# MotorDriver.net
KiCad netlist of a schematic drawn in Altium Designer
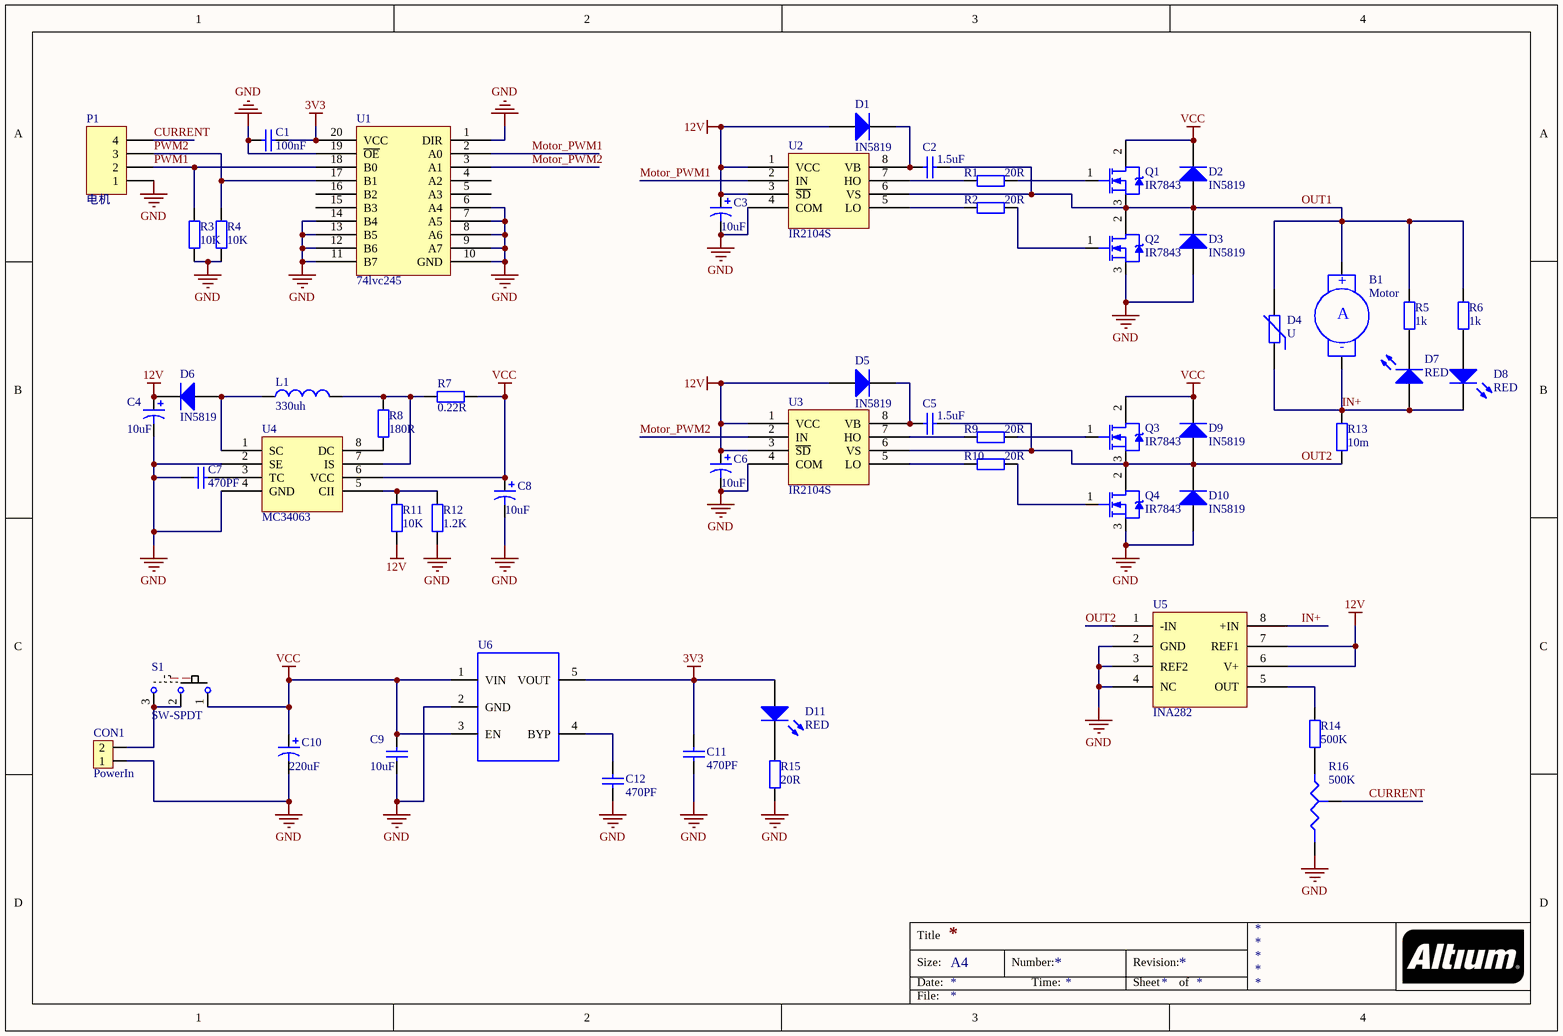
[diagram p0: MotorDriver.SchDoc]

(export (version "E")
  (design (tool "Eeschema 10.0.6"))
  (components
    (comp (ref "B1")
      (value "Motor")
      (footprint "KF301-2P")
      (description "Servo Motor")
      (libsource (lib "MOS motor driving module ") (part "Motor Servo"))
    )
    (comp (ref "C1")
      (value "100nF")
      (footprint "0603C")
      (description "Capacitor")
      (fields (field (name "Comment") "Cap") (field (name "PUBLISHER") "Altium Limited"))
      (libsource (lib "MOS motor driving module ") (part "Cap"))
    )
    (comp (ref "C2")
      (value "1.5uF")
      (footprint "0603C")
      (description "Capacitor")
      (fields (field (name "Comment") "Cap") (field (name "PUBLISHER") "Altium Limited"))
      (libsource (lib "MOS motor driving module ") (part "Cap"))
    )
    (comp (ref "C3")
      (value "10uF")
      (footprint "0603C")
      (description "Polarized Capacitor (Radial)")
      (fields (field (name "Comment") "Cap Pol1") (field (name "PUBLISHER") "Altium Limited"))
      (libsource (lib "MOS motor driving module ") (part "Cap Pol1"))
    )
    (comp (ref "C4")
      (value "10uF")
      (footprint "0603C")
      (description "Polarized Capacitor (Radial)")
      (fields (field (name "Comment") "Cap Pol1") (field (name "PUBLISHER") "Altium Limited"))
      (libsource (lib "MOS motor driving module ") (part "Cap Pol1"))
    )
    (comp (ref "C5")
      (value "1.5uF")
      (footprint "0603C")
      (description "Capacitor")
      (fields (field (name "Comment") "Cap") (field (name "PUBLISHER") "Altium Limited"))
      (libsource (lib "MOS motor driving module ") (part "Cap"))
    )
    (comp (ref "C6")
      (value "10uF")
      (footprint "0603C")
      (description "Polarized Capacitor (Radial)")
      (fields (field (name "Comment") "Cap Pol1") (field (name "PUBLISHER") "Altium Limited"))
      (libsource (lib "MOS motor driving module ") (part "Cap Pol1"))
    )
    (comp (ref "C7")
      (value "470PF")
      (footprint "0603C")
      (description "Capacitor")
      (fields (field (name "Comment") "Cap") (field (name "PUBLISHER") "Altium Limited"))
      (libsource (lib "MOS motor driving module ") (part "Cap"))
    )
    (comp (ref "C8")
      (value "10uF")
      (footprint "0603C")
      (description "Polarized Capacitor (Radial)")
      (fields (field (name "Comment") "Cap Pol1") (field (name "PUBLISHER") "Altium Limited"))
      (libsource (lib "MOS motor driving module ") (part "Cap Pol1"))
    )
    (comp (ref "C9")
      (value "10uF")
      (footprint "0603C")
      (description "Capacitor")
      (fields (field (name "Comment") "Cap") (field (name "PUBLISHER") "Altium Limited"))
      (libsource (lib "MOS motor driving module ") (part "Cap"))
    )
    (comp (ref "C10")
      (value "220uF")
      (footprint "Cap-Pol-220uf16V")
      (description "Polarized Capacitor (Radial)")
      (fields (field (name "Comment") "Cap Pol1") (field (name "PUBLISHER") "Altium Limited"))
      (libsource (lib "MOS motor driving module ") (part "Cap Pol1"))
    )
    (comp (ref "C11")
      (value "470PF")
      (footprint "0603C")
      (description "Capacitor")
      (fields (field (name "Comment") "Cap") (field (name "PUBLISHER") "Altium Limited"))
      (libsource (lib "MOS motor driving module ") (part "Cap"))
    )
    (comp (ref "C12")
      (value "470PF")
      (footprint "0603C")
      (description "Capacitor")
      (fields (field (name "Comment") "Cap") (field (name "PUBLISHER") "Altium Limited"))
      (libsource (lib "MOS motor driving module ") (part "Cap"))
    )
    (comp (ref "CON1")
      (value "PowerIn")
      (footprint "KF301-2P")
      (description "Header, 2-Pin")
      (libsource (lib "MOS motor driving module ") (part "Header 2"))
    )
    (comp (ref "D1")
      (value "IN5819")
      (footprint "DL-41 - duplicate")
      (description "Default Diode")
      (libsource (lib "MOS motor driving module ") (part "Diode"))
    )
    (comp (ref "D2")
      (value "IN5819")
      (footprint "DL-41 - duplicate")
      (description "Default Diode")
      (libsource (lib "MOS motor driving module ") (part "Diode"))
    )
    (comp (ref "D3")
      (value "IN5819")
      (footprint "DL-41 - duplicate")
      (description "Default Diode")
      (libsource (lib "MOS motor driving module ") (part "Diode"))
    )
    (comp (ref "D4")
      (value "U")
      (footprint "0805(2012)")
      (description "Varistor (Voltage-Sensitive Resistor)")
      (fields (field (name "PUBLISHER") "Altium Limited"))
      (libsource (lib "MOS motor driving module ") (part "Res Varistor"))
    )
    (comp (ref "D5")
      (value "IN5819")
      (footprint "DL-41")
      (description "Default Diode")
      (libsource (lib "MOS motor driving module ") (part "Diode"))
    )
    (comp (ref "D6")
      (value "IN5819")
      (footprint "DL-41 - duplicate")
      (description "Default Diode")
      (libsource (lib "MOS motor driving module ") (part "Diode"))
    )
    (comp (ref "D7")
      (value "RED")
      (footprint "0805LED")
      (description "Typical RED, GREEN, YELLOW, AMBER GaAs LED")
      (fields (field (name "PUBLISHER") "Altium Limited"))
      (libsource (lib "MOS motor driving module ") (part "LED2"))
    )
    (comp (ref "D8")
      (value "RED")
      (footprint "0805LED")
      (description "Typical RED, GREEN, YELLOW, AMBER GaAs LED")
      (fields (field (name "PUBLISHER") "Altium Limited"))
      (libsource (lib "MOS motor driving module ") (part "LED2"))
    )
    (comp (ref "D9")
      (value "IN5819")
      (footprint "DL-41 - duplicate")
      (description "Default Diode")
      (libsource (lib "MOS motor driving module ") (part "Diode"))
    )
    (comp (ref "D10")
      (value "IN5819")
      (footprint "DL-41 - duplicate")
      (description "Default Diode")
      (libsource (lib "MOS motor driving module ") (part "Diode"))
    )
    (comp (ref "D11")
      (value "RED")
      (footprint "0805LED")
      (description "Typical RED, GREEN, YELLOW, AMBER GaAs LED")
      (fields (field (name "PUBLISHER") "Altium Limited"))
      (libsource (lib "MOS motor driving module ") (part "LED2"))
    )
    (comp (ref "L1")
      (value "330uh")
      (footprint "电感8*8_1")
      (description "Inductor")
      (fields (field (name "PUBLISHER") "Altium Limited"))
      (libsource (lib "MOS motor driving module ") (part "Inductor"))
    )
    (comp (ref "P1")
      (value "电机")
      (footprint "XH1X4")
      (description "Header, 4-Pin")
      (fields (field (name "PUBLISHER") "Altium Limited"))
      (libsource (lib "My") (part "Header 4"))
    )
    (comp (ref "Q1")
      (value "IR7843")
      (footprint "LR7843")
      (description "N-Channel Power MOSFET")
      (fields (field (name "PUBLISHER") "Altium Limited"))
      (libsource (lib "MOS motor driving module ") (part "NMOS-2"))
    )
    (comp (ref "Q2")
      (value "IR7843")
      (footprint "LR7843")
      (description "N-Channel Power MOSFET")
      (fields (field (name "PUBLISHER") "Altium Limited"))
      (libsource (lib "MOS motor driving module ") (part "NMOS-2"))
    )
    (comp (ref "Q3")
      (value "IR7843")
      (footprint "LR7843")
      (description "N-Channel Power MOSFET")
      (fields (field (name "PUBLISHER") "Altium Limited"))
      (libsource (lib "MOS motor driving module ") (part "NMOS-2"))
    )
    (comp (ref "Q4")
      (value "IR7843")
      (footprint "LR7843")
      (description "N-Channel Power MOSFET")
      (fields (field (name "PUBLISHER") "Altium Limited"))
      (libsource (lib "MOS motor driving module ") (part "NMOS-2"))
    )
    (comp (ref "R1")
      (value "20R")
      (footprint "0603R")
      (description "Resistor")
      (fields (field (name "Comment") "Res2") (field (name "PUBLISHER") "Altium Limited"))
      (libsource (lib "") (part "Res2_2"))
    )
    (comp (ref "R2")
      (value "20R")
      (footprint "0603R")
      (description "Resistor")
      (fields (field (name "Comment") "Res2") (field (name "PUBLISHER") "Altium Limited"))
      (libsource (lib "") (part "Res2_2"))
    )
    (comp (ref "R3")
      (value "10K")
      (footprint "0603R")
      (description "Resistor")
      (fields (field (name "Comment") "Res2") (field (name "PUBLISHER") "Altium Limited"))
      (libsource (lib "MOS motor driving module ") (part "Res2"))
    )
    (comp (ref "R4")
      (value "10K")
      (footprint "0603R")
      (description "Resistor")
      (fields (field (name "Comment") "Res2") (field (name "PUBLISHER") "Altium Limited"))
      (libsource (lib "MOS motor driving module ") (part "Res2"))
    )
    (comp (ref "R5")
      (value "1k")
      (footprint "0603R")
      (description "Resistor")
      (fields (field (name "Comment") "Res2") (field (name "PUBLISHER") "Altium Limited"))
      (libsource (lib "") (part "Res2_1"))
    )
    (comp (ref "R6")
      (value "1k")
      (footprint "0603R")
      (description "Resistor")
      (fields (field (name "Comment") "Res2") (field (name "PUBLISHER") "Altium Limited"))
      (libsource (lib "") (part "Res2_1"))
    )
    (comp (ref "R7")
      (value "0.22R")
      (footprint "0603R")
      (description "Resistor")
      (fields (field (name "Comment") "Res2") (field (name "PUBLISHER") "Altium Limited"))
      (libsource (lib "") (part "Res2_3"))
    )
    (comp (ref "R8")
      (value "180R")
      (footprint "0603R")
      (description "Resistor")
      (fields (field (name "Comment") "Res2") (field (name "PUBLISHER") "Altium Limited"))
      (libsource (lib "") (part "Res2_1"))
    )
    (comp (ref "R9")
      (value "20R")
      (footprint "0603R")
      (description "Resistor")
      (fields (field (name "Comment") "Res2") (field (name "PUBLISHER") "Altium Limited"))
      (libsource (lib "") (part "Res2_2"))
    )
    (comp (ref "R10")
      (value "20R")
      (footprint "0603R")
      (description "Resistor")
      (fields (field (name "Comment") "Res2") (field (name "PUBLISHER") "Altium Limited"))
      (libsource (lib "") (part "Res2_2"))
    )
    (comp (ref "R11")
      (value "10K")
      (footprint "0603R")
      (description "Resistor")
      (fields (field (name "Comment") "Res2") (field (name "PUBLISHER") "Altium Limited"))
      (libsource (lib "MOS motor driving module ") (part "Res2"))
    )
    (comp (ref "R12")
      (value "1.2K")
      (footprint "0603R")
      (description "Resistor")
      (fields (field (name "Comment") "Res2") (field (name "PUBLISHER") "Altium Limited"))
      (libsource (lib "MOS motor driving module ") (part "Res2"))
    )
    (comp (ref "R13")
      (value "10m")
      (footprint "0603R")
      (description "Resistor")
      (fields (field (name "Comment") "Res2") (field (name "PUBLISHER") "Altium Limited"))
      (libsource (lib "") (part "Res2_1"))
    )
    (comp (ref "R14")
      (value "500K")
      (footprint "0603R")
      (description "Resistor")
      (fields (field (name "Comment") "Res2") (field (name "PUBLISHER") "Altium Limited"))
      (libsource (lib "") (part "Res2_1"))
    )
    (comp (ref "R15")
      (value "20R")
      (footprint "0603R")
      (description "Resistor")
      (fields (field (name "Comment") "Res2") (field (name "PUBLISHER") "Altium Limited"))
      (libsource (lib "") (part "Res2_1"))
    )
    (comp (ref "R16") (value "500K") (footprint "VR_3362P") (libsource (lib "1209Lab") (part "RES-ADJ")))
    (comp (ref "S1")
      (value "SW-SPDT")
      (footprint "SWICH_2")
      (description "SPDT Subminiature Toggle Switch, Right Angle Mounting, Vertical Actuation")
      (libsource (lib "MOS motor driving module ") (part "SW-SPDT"))
    )
    (comp (ref "U1")
      (value "74lvc245")
      (footprint "74lvc245 TSSOP")
      (description "8位5伏转3.3伏电平转换芯片")
      (libsource (lib "MOS motor driving module ") (part "74lvc245"))
    )
    (comp (ref "U2") (value "IR2104S") (footprint "SOIC-8") (libsource (lib "My") (part "IR2104S")))
    (comp (ref "U3") (value "IR2104S") (footprint "SOIC-8") (libsource (lib "My") (part "IR2104S")))
    (comp (ref "U4") (value "MC34063") (footprint "SOIC-8") (libsource (lib "My") (part "MC34063")))
    (comp (ref "U5") (value "INA282") (footprint "SOIC-8") (libsource (lib "My") (part "INA282")))
    (comp (ref "U6")
      (value "MIC5219")
      (footprint "SOT23-5")
      (description "LDO")
      (libsource (lib "MOS motor driving module ") (part "MIC5219"))
    )
  )
  (nets
    (net (code "1") (name "/CURRENT") (class "Default")
      (node (ref "P1") (pin "4") (pinfunction "4_4") (pintype "passive"))
      (node (ref "R16") (pin "2") (pinfunction "2_2") (pintype "passive"))
    )
    (net (code "2") (name "/IN+") (class "Default")
      (node (ref "B1") (pin "2") (pinfunction "-_2") (pintype "passive"))
      (node (ref "D4") (pin "1") (pinfunction "1_1") (pintype "passive"))
      (node (ref "D7") (pin "1") (pinfunction "A_1") (pintype "passive"))
      (node (ref "D8") (pin "2") (pinfunction "K_2") (pintype "passive"))
      (node (ref "R13") (pin "2") (pinfunction "2_2") (pintype "passive"))
      (node (ref "U5") (pin "8") (pinfunction "+IN_8") (pintype "passive"))
    )
    (net (code "3") (name "/Motor_PWM1") (class "Default")
      (node (ref "U1") (pin "2") (pinfunction "A0_2") (pintype "passive"))
      (node (ref "U2") (pin "2") (pinfunction "IN_2") (pintype "passive"))
    )
    (net (code "4") (name "/Motor_PWM2") (class "Default")
      (node (ref "U1") (pin "3") (pinfunction "A1_3") (pintype "passive"))
      (node (ref "U3") (pin "2") (pinfunction "IN_2") (pintype "passive"))
    )
    (net (code "5") (name "/OUT1") (class "Default")
      (node (ref "B1") (pin "1") (pinfunction "+_1") (pintype "passive"))
      (node (ref "C2") (pin "2") (pinfunction "2_2") (pintype "passive"))
      (node (ref "D2") (pin "1") (pinfunction "A_1") (pintype "passive"))
      (node (ref "D3") (pin "2") (pinfunction "K_2") (pintype "passive"))
      (node (ref "D4") (pin "2") (pinfunction "2_2") (pintype "passive"))
      (node (ref "Q1") (pin "3") (pinfunction "S_3") (pintype "passive"))
      (node (ref "Q2") (pin "2") (pinfunction "D_2") (pintype "passive"))
      (node (ref "R5") (pin "2") (pinfunction "2_2") (pintype "passive"))
      (node (ref "R6") (pin "2") (pinfunction "2_2") (pintype "passive"))
      (node (ref "U2") (pin "6") (pinfunction "VS_6") (pintype "passive"))
    )
    (net (code "6") (name "/OUT2") (class "Default")
      (node (ref "C5") (pin "2") (pinfunction "2_2") (pintype "passive"))
      (node (ref "D10") (pin "2") (pinfunction "K_2") (pintype "passive"))
      (node (ref "D9") (pin "1") (pinfunction "A_1") (pintype "passive"))
      (node (ref "Q3") (pin "3") (pinfunction "S_3") (pintype "passive"))
      (node (ref "Q4") (pin "2") (pinfunction "D_2") (pintype "passive"))
      (node (ref "R13") (pin "1") (pinfunction "1_1") (pintype "passive"))
      (node (ref "U3") (pin "6") (pinfunction "VS_6") (pintype "passive"))
      (node (ref "U5") (pin "1") (pinfunction "-IN_1") (pintype "passive"))
    )
    (net (code "7") (name "/PWM1") (class "Default")
      (node (ref "P1") (pin "2") (pinfunction "2_2") (pintype "passive"))
      (node (ref "R3") (pin "1") (pinfunction "1_1") (pintype "passive"))
      (node (ref "U1") (pin "18") (pinfunction "B0_18") (pintype "passive"))
    )
    (net (code "8") (name "/PWM2") (class "Default")
      (node (ref "P1") (pin "3") (pinfunction "3_3") (pintype "passive"))
      (node (ref "R4") (pin "1") (pinfunction "1_1") (pintype "passive"))
      (node (ref "U1") (pin "17") (pinfunction "B1_17") (pintype "passive"))
    )
    (net (code "9") (name "3V3") (class "Default")
      (node (ref "C1") (pin "1") (pinfunction "1_1") (pintype "passive"))
      (node (ref "C11") (pin "2") (pinfunction "2_2") (pintype "passive"))
      (node (ref "D11") (pin "1") (pinfunction "A_1") (pintype "passive"))
      (node (ref "U1") (pin "20") (pinfunction "VCC_20") (pintype "passive"))
      (node (ref "U6") (pin "5") (pinfunction "VOUT_5") (pintype "passive"))
    )
    (net (code "10") (name "12V") (class "Default")
      (node (ref "C3") (pin "1") (pinfunction "1_1") (pintype "passive"))
      (node (ref "C4") (pin "1") (pinfunction "1_1") (pintype "passive"))
      (node (ref "C6") (pin "1") (pinfunction "1_1") (pintype "passive"))
      (node (ref "D1") (pin "1") (pinfunction "A_1") (pintype "passive"))
      (node (ref "D5") (pin "1") (pinfunction "A_1") (pintype "passive"))
      (node (ref "D6") (pin "2") (pinfunction "K_2") (pintype "passive"))
      (node (ref "R11") (pin "2") (pinfunction "2_2") (pintype "passive"))
      (node (ref "U2") (pin "1") (pinfunction "VCC_1") (pintype "passive"))
      (node (ref "U2") (pin "3") (pinfunction "~{SD}_3") (pintype "passive"))
      (node (ref "U3") (pin "1") (pinfunction "VCC_1") (pintype "passive"))
      (node (ref "U3") (pin "3") (pinfunction "~{SD}_3") (pintype "passive"))
      (node (ref "U5") (pin "6") (pinfunction "V+_6") (pintype "passive"))
      (node (ref "U5") (pin "7") (pinfunction "REF1_7") (pintype "passive"))
    )
    (net (code "11") (name "GND") (class "Default")
      (node (ref "C1") (pin "2") (pinfunction "2_2") (pintype "passive"))
      (node (ref "C10") (pin "2") (pinfunction "2_2") (pintype "passive"))
      (node (ref "C11") (pin "1") (pinfunction "1_1") (pintype "passive"))
      (node (ref "C12") (pin "1") (pinfunction "1_1") (pintype "passive"))
      (node (ref "C3") (pin "2") (pinfunction "2_2") (pintype "passive"))
      (node (ref "C4") (pin "2") (pinfunction "2_2") (pintype "passive"))
      (node (ref "C6") (pin "2") (pinfunction "2_2") (pintype "passive"))
      (node (ref "C7") (pin "2") (pinfunction "2_2") (pintype "passive"))
      (node (ref "C8") (pin "2") (pinfunction "2_2") (pintype "passive"))
      (node (ref "C9") (pin "1") (pinfunction "1_1") (pintype "passive"))
      (node (ref "CON1") (pin "1") (pinfunction "1_1") (pintype "passive"))
      (node (ref "D10") (pin "1") (pinfunction "A_1") (pintype "passive"))
      (node (ref "D3") (pin "1") (pinfunction "A_1") (pintype "passive"))
      (node (ref "P1") (pin "1") (pinfunction "1_1") (pintype "passive"))
      (node (ref "Q2") (pin "3") (pinfunction "S_3") (pintype "passive"))
      (node (ref "Q4") (pin "3") (pinfunction "S_3") (pintype "passive"))
      (node (ref "R12") (pin "2") (pinfunction "2_2") (pintype "passive"))
      (node (ref "R15") (pin "1") (pinfunction "1_1") (pintype "passive"))
      (node (ref "R16") (pin "3") (pinfunction "3_3") (pintype "passive"))
      (node (ref "R3") (pin "2") (pinfunction "2_2") (pintype "passive"))
      (node (ref "R4") (pin "2") (pinfunction "2_2") (pintype "passive"))
      (node (ref "U1") (pin "1") (pinfunction "DIR_1") (pintype "passive"))
      (node (ref "U1") (pin "10") (pinfunction "GND_10") (pintype "passive"))
      (node (ref "U1") (pin "11") (pinfunction "B7_11") (pintype "passive"))
      (node (ref "U1") (pin "12") (pinfunction "B6_12") (pintype "passive"))
      (node (ref "U1") (pin "13") (pinfunction "B5_13") (pintype "passive"))
      (node (ref "U1") (pin "14") (pinfunction "B4_14") (pintype "passive"))
      (node (ref "U1") (pin "19") (pinfunction "~{OE}_19") (pintype "passive"))
      (node (ref "U1") (pin "6") (pinfunction "A4_6") (pintype "passive"))
      (node (ref "U1") (pin "7") (pinfunction "A5_7") (pintype "passive"))
      (node (ref "U1") (pin "8") (pinfunction "A6_8") (pintype "passive"))
      (node (ref "U1") (pin "9") (pinfunction "A7_9") (pintype "passive"))
      (node (ref "U2") (pin "4") (pinfunction "COM_4") (pintype "passive"))
      (node (ref "U3") (pin "4") (pinfunction "COM_4") (pintype "passive"))
      (node (ref "U4") (pin "2") (pinfunction "SE_2") (pintype "passive"))
      (node (ref "U4") (pin "4") (pinfunction "GND_4") (pintype "passive"))
      (node (ref "U5") (pin "2") (pinfunction "GND_2") (pintype "passive"))
      (node (ref "U5") (pin "3") (pinfunction "REF2_3") (pintype "passive"))
      (node (ref "U5") (pin "4") (pinfunction "NC_4") (pintype "passive"))
      (node (ref "U6") (pin "2") (pinfunction "GND_2") (pintype "passive"))
    )
    (net (code "12") (name "Net-(CON1-Pad2)") (class "Default")
      (node (ref "CON1") (pin "2") (pinfunction "2_2") (pintype "passive"))
      (node (ref "S1") (pin "2") (pinfunction "2_2") (pintype "passive"))
      (node (ref "S1") (pin "3") (pinfunction "3_3") (pintype "passive"))
    )
    (net (code "13") (name "Net-(D1-K)") (class "Default")
      (node (ref "C2") (pin "1") (pinfunction "1_1") (pintype "passive"))
      (node (ref "D1") (pin "2") (pinfunction "K_2") (pintype "passive"))
      (node (ref "U2") (pin "8") (pinfunction "VB_8") (pintype "passive"))
    )
    (net (code "14") (name "Net-(D5-K)") (class "Default")
      (node (ref "C5") (pin "1") (pinfunction "1_1") (pintype "passive"))
      (node (ref "D5") (pin "2") (pinfunction "K_2") (pintype "passive"))
      (node (ref "U3") (pin "8") (pinfunction "VB_8") (pintype "passive"))
    )
    (net (code "15") (name "Net-(D6-A)") (class "Default")
      (node (ref "D6") (pin "1") (pinfunction "A_1") (pintype "passive"))
      (node (ref "L1") (pin "1") (pinfunction "1_1") (pintype "passive"))
      (node (ref "U4") (pin "1") (pinfunction "SC_1") (pintype "passive"))
    )
    (net (code "16") (name "Net-(D7-K)") (class "Default")
      (node (ref "D7") (pin "2") (pinfunction "K_2") (pintype "passive"))
      (node (ref "R5") (pin "1") (pinfunction "1_1") (pintype "passive"))
    )
    (net (code "17") (name "Net-(D8-A)") (class "Default")
      (node (ref "D8") (pin "1") (pinfunction "A_1") (pintype "passive"))
      (node (ref "R6") (pin "1") (pinfunction "1_1") (pintype "passive"))
    )
    (net (code "18") (name "Net-(D11-K)") (class "Default")
      (node (ref "D11") (pin "2") (pinfunction "K_2") (pintype "passive"))
      (node (ref "R15") (pin "2") (pinfunction "2_2") (pintype "passive"))
    )
    (net (code "19") (name "Net-(Q1-G)") (class "Default")
      (node (ref "Q1") (pin "1") (pinfunction "G_1") (pintype "passive"))
      (node (ref "R1") (pin "2") (pinfunction "2_2") (pintype "passive"))
    )
    (net (code "20") (name "Net-(Q2-G)") (class "Default")
      (node (ref "Q2") (pin "1") (pinfunction "G_1") (pintype "passive"))
      (node (ref "R2") (pin "2") (pinfunction "2_2") (pintype "passive"))
    )
    (net (code "21") (name "Net-(Q3-G)") (class "Default")
      (node (ref "Q3") (pin "1") (pinfunction "G_1") (pintype "passive"))
      (node (ref "R9") (pin "2") (pinfunction "2_2") (pintype "passive"))
    )
    (net (code "22") (name "Net-(Q4-G)") (class "Default")
      (node (ref "Q4") (pin "1") (pinfunction "G_1") (pintype "passive"))
      (node (ref "R10") (pin "2") (pinfunction "2_2") (pintype "passive"))
    )
    (net (code "23") (name "Net-(R14-Pad1)") (class "Default")
      (node (ref "R14") (pin "1") (pinfunction "1_1") (pintype "passive"))
      (node (ref "R16") (pin "1") (pinfunction "1_1") (pintype "passive"))
    )
    (net (code "24") (name "Net-(U2-HO)") (class "Default")
      (node (ref "R1") (pin "1") (pinfunction "1_1") (pintype "passive"))
      (node (ref "U2") (pin "7") (pinfunction "HO_7") (pintype "passive"))
    )
    (net (code "25") (name "Net-(U2-LO)") (class "Default")
      (node (ref "R2") (pin "1") (pinfunction "1_1") (pintype "passive"))
      (node (ref "U2") (pin "5") (pinfunction "LO_5") (pintype "passive"))
    )
    (net (code "26") (name "Net-(U3-HO)") (class "Default")
      (node (ref "R9") (pin "1") (pinfunction "1_1") (pintype "passive"))
      (node (ref "U3") (pin "7") (pinfunction "HO_7") (pintype "passive"))
    )
    (net (code "27") (name "Net-(U3-LO)") (class "Default")
      (node (ref "R10") (pin "1") (pinfunction "1_1") (pintype "passive"))
      (node (ref "U3") (pin "5") (pinfunction "LO_5") (pintype "passive"))
    )
    (net (code "28") (name "Net-(U4-CII)") (class "Default")
      (node (ref "R11") (pin "1") (pinfunction "1_1") (pintype "passive"))
      (node (ref "R12") (pin "1") (pinfunction "1_1") (pintype "passive"))
      (node (ref "U4") (pin "5") (pinfunction "CII_5") (pintype "passive"))
    )
    (net (code "29") (name "Net-(U4-DC)") (class "Default")
      (node (ref "R8") (pin "1") (pinfunction "1_1") (pintype "passive"))
      (node (ref "U4") (pin "8") (pinfunction "DC_8") (pintype "passive"))
    )
    (net (code "30") (name "Net-(U4-IS)") (class "Default")
      (node (ref "L1") (pin "2") (pinfunction "2_2") (pintype "passive"))
      (node (ref "R7") (pin "2") (pinfunction "2_2") (pintype "passive"))
      (node (ref "R8") (pin "2") (pinfunction "2_2") (pintype "passive"))
      (node (ref "U4") (pin "7") (pinfunction "IS_7") (pintype "passive"))
    )
    (net (code "31") (name "Net-(U4-TC)") (class "Default")
      (node (ref "C7") (pin "1") (pinfunction "1_1") (pintype "passive"))
      (node (ref "U4") (pin "3") (pinfunction "TC_3") (pintype "passive"))
    )
    (net (code "32") (name "Net-(U5-OUT)") (class "Default")
      (node (ref "R14") (pin "2") (pinfunction "2_2") (pintype "passive"))
      (node (ref "U5") (pin "5") (pinfunction "OUT_5") (pintype "passive"))
    )
    (net (code "33") (name "Net-(U6-BYP)") (class "Default")
      (node (ref "C12") (pin "2") (pinfunction "2_2") (pintype "passive"))
      (node (ref "U6") (pin "4") (pinfunction "BYP_4") (pintype "passive"))
    )
    (net (code "34") (name "VCC") (class "Default")
      (node (ref "C10") (pin "1") (pinfunction "1_1") (pintype "passive"))
      (node (ref "C8") (pin "1") (pinfunction "1_1") (pintype "passive"))
      (node (ref "C9") (pin "2") (pinfunction "2_2") (pintype "passive"))
      (node (ref "D2") (pin "2") (pinfunction "K_2") (pintype "passive"))
      (node (ref "D9") (pin "2") (pinfunction "K_2") (pintype "passive"))
      (node (ref "Q1") (pin "2") (pinfunction "D_2") (pintype "passive"))
      (node (ref "Q3") (pin "2") (pinfunction "D_2") (pintype "passive"))
      (node (ref "R7") (pin "1") (pinfunction "1_1") (pintype "passive"))
      (node (ref "S1") (pin "1") (pinfunction "1_1") (pintype "passive"))
      (node (ref "U4") (pin "6") (pinfunction "VCC_6") (pintype "passive"))
      (node (ref "U6") (pin "1") (pinfunction "VIN_1") (pintype "passive"))
      (node (ref "U6") (pin "3") (pinfunction "EN_3") (pintype "passive"))
    )
    (net (code "35") (name "unconnected-(U1-A2-Pad4)") (class "Default")
      (node (ref "U1") (pin "4") (pinfunction "A2_4") (pintype "passive"))
    )
    (net (code "36") (name "unconnected-(U1-A3-Pad5)") (class "Default")
      (node (ref "U1") (pin "5") (pinfunction "A3_5") (pintype "passive"))
    )
    (net (code "37") (name "unconnected-(U1-B2-Pad16)") (class "Default")
      (node (ref "U1") (pin "16") (pinfunction "B2_16") (pintype "passive"))
    )
    (net (code "38") (name "unconnected-(U1-B3-Pad15)") (class "Default")
      (node (ref "U1") (pin "15") (pinfunction "B3_15") (pintype "passive"))
    )
  )
)
